# TriggerPI.net
KiCad netlist of a schematic drawn in EAGLE
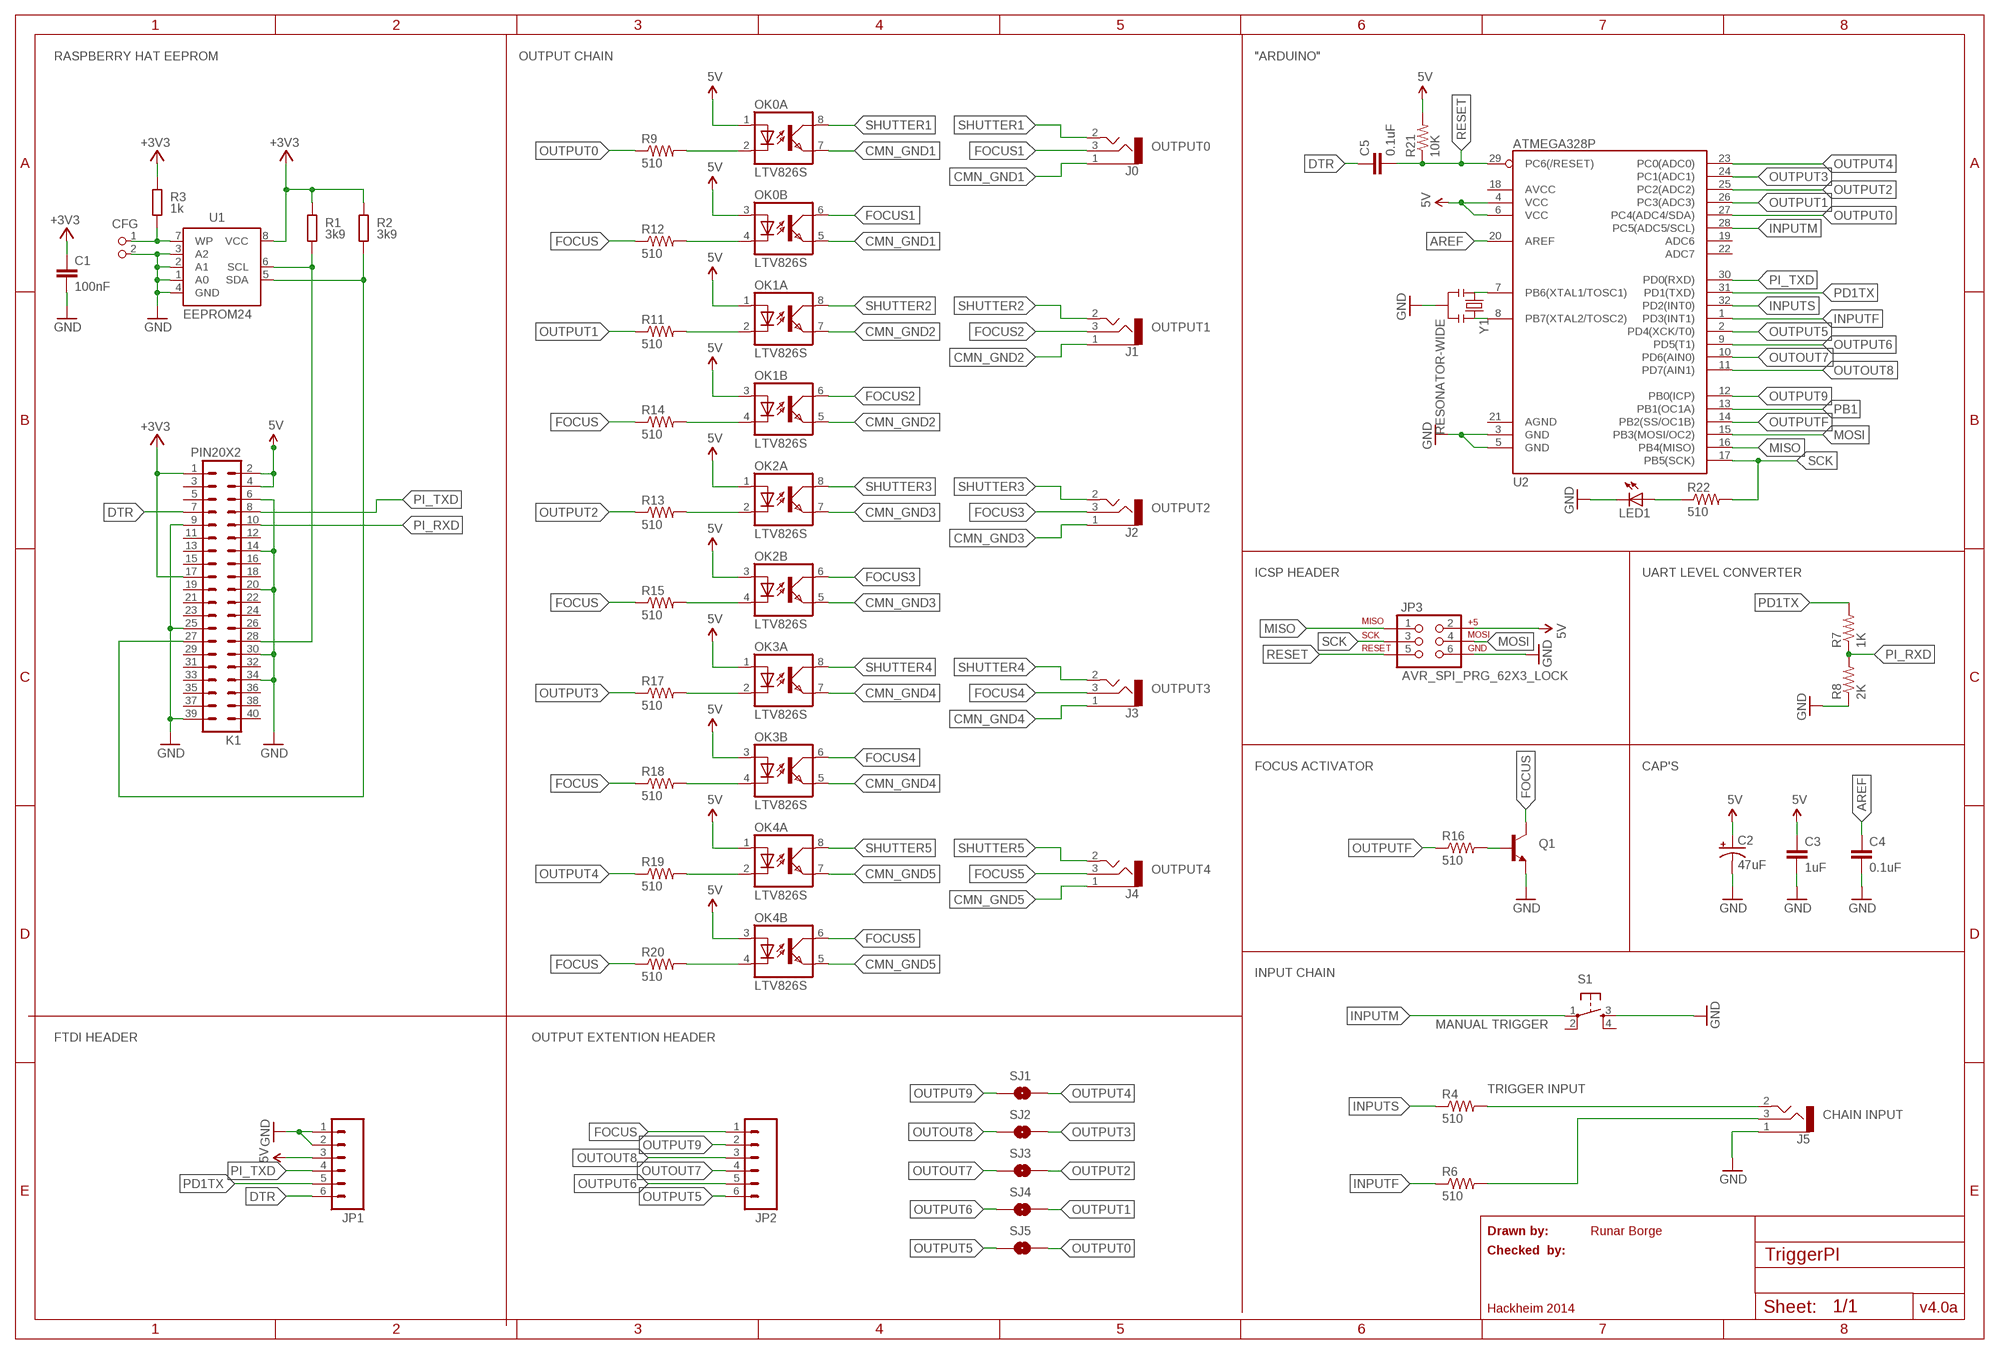
[diagram p0: schematic, sheet 1]

(export (version "E")
  (design (tool "Eeschema 10.0.6"))
  (components
    (comp (ref "C1")
      (value "100nF")
      (footprint "eagle-import:C0805K")
      (libsource (lib "eagle-import") (part "C-EUC0805K"))
    )
    (comp (ref "C2")
      (value "47uF")
      (footprint "eagle-import:EIA3528")
      (libsource (lib "eagle-import") (part "47UF-TANT"))
    )
    (comp (ref "C3")
      (value "1uF")
      (footprint "eagle-import:0805")
      (libsource (lib "eagle-import") (part "1UF-25V-10%(0805)"))
    )
    (comp (ref "C4")
      (value "0.1uF")
      (footprint "eagle-import:0603-CAP")
      (libsource (lib "eagle-import") (part "CAP0603-CAP"))
    )
    (comp (ref "C5")
      (value "0.1uF")
      (footprint "eagle-import:0603-CAP")
      (libsource (lib "eagle-import") (part "CAP0603-CAP"))
    )
    (comp (ref "CFG")
      (value "PIN2_100")
      (footprint "eagle-import:PIN_W_2")
      (libsource (lib "eagle-import") (part "PIN2_100"))
    )
    (comp (ref "J0")
      (value "AUDIO-3P'SJ-3523-SMT'")
      (footprint "eagle-import:3P-SMD-3.5")
      (libsource (lib "eagle-import") (part "AUDIO-3P'SJ-3523-SMT'"))
    )
    (comp (ref "J1")
      (value "AUDIO-3P'SJ-3523-SMT'")
      (footprint "eagle-import:3P-SMD-3.5")
      (libsource (lib "eagle-import") (part "AUDIO-3P'SJ-3523-SMT'"))
    )
    (comp (ref "J2")
      (value "AUDIO-3P'SJ-3523-SMT'")
      (footprint "eagle-import:3P-SMD-3.5")
      (libsource (lib "eagle-import") (part "AUDIO-3P'SJ-3523-SMT'"))
    )
    (comp (ref "J3")
      (value "AUDIO-3P'SJ-3523-SMT'")
      (footprint "eagle-import:3P-SMD-3.5")
      (libsource (lib "eagle-import") (part "AUDIO-3P'SJ-3523-SMT'"))
    )
    (comp (ref "J4")
      (value "AUDIO-3P'SJ-3523-SMT'")
      (footprint "eagle-import:3P-SMD-3.5")
      (libsource (lib "eagle-import") (part "AUDIO-3P'SJ-3523-SMT'"))
    )
    (comp (ref "J5")
      (value "AUDIO-3P'SJ-3523-SMT'")
      (footprint "eagle-import:3P-SMD-3.5")
      (libsource (lib "eagle-import") (part "AUDIO-3P'SJ-3523-SMT'"))
    )
    (comp (ref "JP1")
      (value "M06LOCK")
      (footprint "eagle-import:1X06_LOCK")
      (libsource (lib "eagle-import") (part "M06LOCK"))
    )
    (comp (ref "JP2")
      (value "M06LOCK")
      (footprint "eagle-import:1X06_LOCK")
      (libsource (lib "eagle-import") (part "M06LOCK"))
    )
    (comp (ref "JP3")
      (value "AVR_SPI_PRG_62X3_LOCK")
      (footprint "eagle-import:2X3_LOCK")
      (libsource (lib "eagle-import") (part "AVR_SPI_PRG_62X3_LOCK"))
    )
    (comp (ref "K1")
      (value "PIN20X2")
      (footprint "eagle-import:PIN_20X2")
      (libsource (lib "eagle-import") (part "PIN20X2"))
    )
    (comp (ref "LED1")
      (value "LED1206")
      (footprint "eagle-import:LED-1206")
      (libsource (lib "eagle-import") (part "LED1206"))
    )
    (comp (ref "OK0")
      (value "LTV826S")
      (footprint "eagle-import:DIL8-SMD")
      (fields (field (name "DIGIKEY") "160-1363-5-ND"))
      (libsource (lib "eagle-import") (part "LTV826S"))
    )
    (comp (ref "OK1")
      (value "LTV826S")
      (footprint "eagle-import:DIL8-SMD")
      (fields (field (name "DIGIKEY") "160-1363-5-ND"))
      (libsource (lib "eagle-import") (part "LTV826S"))
    )
    (comp (ref "OK2")
      (value "LTV826S")
      (footprint "eagle-import:DIL8-SMD")
      (fields (field (name "DIGIKEY") "160-1363-5-ND"))
      (libsource (lib "eagle-import") (part "LTV826S"))
    )
    (comp (ref "OK3")
      (value "LTV826S")
      (footprint "eagle-import:DIL8-SMD")
      (fields (field (name "DIGIKEY") "160-1363-5-ND"))
      (libsource (lib "eagle-import") (part "LTV826S"))
    )
    (comp (ref "OK4")
      (value "LTV826S")
      (footprint "eagle-import:DIL8-SMD")
      (fields (field (name "DIGIKEY") "160-1363-5-ND"))
      (libsource (lib "eagle-import") (part "LTV826S"))
    )
    (comp (ref "Q1")
      (value "TRANSISTOR_NPNSOT23-3")
      (footprint "eagle-import:SOT23-3")
      (libsource (lib "eagle-import") (part "TRANSISTOR_NPNSOT23-3"))
    )
    (comp (ref "R1")
      (value "3k9")
      (footprint "eagle-import:M0805")
      (fields (field (name "TOLERANCE") "5%"))
      (libsource (lib "eagle-import") (part "R-EU_M0805"))
    )
    (comp (ref "R2")
      (value "3k9")
      (footprint "eagle-import:M0805")
      (fields (field (name "TOLERANCE") "5%"))
      (libsource (lib "eagle-import") (part "R-EU_M0805"))
    )
    (comp (ref "R3")
      (value "1k")
      (footprint "eagle-import:M0805")
      (fields (field (name "TOLERANCE") "5%"))
      (libsource (lib "eagle-import") (part "R-EU_M0805"))
    )
    (comp (ref "R4")
      (value "510")
      (footprint "eagle-import:0603-RES")
      (libsource (lib "eagle-import") (part "RESISTOR0603-RES"))
    )
    (comp (ref "R6")
      (value "510")
      (footprint "eagle-import:0603-RES")
      (libsource (lib "eagle-import") (part "RESISTOR0603-RES"))
    )
    (comp (ref "R7")
      (value "1K")
      (footprint "eagle-import:0603-RES")
      (libsource (lib "eagle-import") (part "RESISTOR0603-RES"))
    )
    (comp (ref "R8")
      (value "2K")
      (footprint "eagle-import:0603-RES")
      (libsource (lib "eagle-import") (part "RESISTOR0603-RES"))
    )
    (comp (ref "R9")
      (value "510")
      (footprint "eagle-import:0603-RES")
      (libsource (lib "eagle-import") (part "RESISTOR0603-RES"))
    )
    (comp (ref "R11")
      (value "510")
      (footprint "eagle-import:0603-RES")
      (libsource (lib "eagle-import") (part "RESISTOR0603-RES"))
    )
    (comp (ref "R12")
      (value "510")
      (footprint "eagle-import:0603-RES")
      (libsource (lib "eagle-import") (part "RESISTOR0603-RES"))
    )
    (comp (ref "R13")
      (value "510")
      (footprint "eagle-import:0603-RES")
      (libsource (lib "eagle-import") (part "RESISTOR0603-RES"))
    )
    (comp (ref "R14")
      (value "510")
      (footprint "eagle-import:0603-RES")
      (libsource (lib "eagle-import") (part "RESISTOR0603-RES"))
    )
    (comp (ref "R15")
      (value "510")
      (footprint "eagle-import:0603-RES")
      (libsource (lib "eagle-import") (part "RESISTOR0603-RES"))
    )
    (comp (ref "R16")
      (value "510")
      (footprint "eagle-import:0603-RES")
      (libsource (lib "eagle-import") (part "RESISTOR0603-RES"))
    )
    (comp (ref "R17")
      (value "510")
      (footprint "eagle-import:0603-RES")
      (libsource (lib "eagle-import") (part "RESISTOR0603-RES"))
    )
    (comp (ref "R18")
      (value "510")
      (footprint "eagle-import:0603-RES")
      (libsource (lib "eagle-import") (part "RESISTOR0603-RES"))
    )
    (comp (ref "R19")
      (value "510")
      (footprint "eagle-import:0603-RES")
      (libsource (lib "eagle-import") (part "RESISTOR0603-RES"))
    )
    (comp (ref "R20")
      (value "510")
      (footprint "eagle-import:0603-RES")
      (libsource (lib "eagle-import") (part "RESISTOR0603-RES"))
    )
    (comp (ref "R21")
      (value "10K")
      (footprint "eagle-import:0603-RES")
      (libsource (lib "eagle-import") (part "RESISTOR0603-RES"))
    )
    (comp (ref "R22")
      (value "510")
      (footprint "eagle-import:0603-RES")
      (libsource (lib "eagle-import") (part "RESISTOR0603-RES"))
    )
    (comp (ref "S1")
      (value "TAC_SWITCHSMD")
      (footprint "eagle-import:TACTILE_SWITCH_SMD")
      (libsource (lib "eagle-import") (part "TAC_SWITCHSMD"))
    )
    (comp (ref "SJ1")
      (value "JUMPER-PAD-2-NOYES_SILK")
      (footprint "eagle-import:PAD-JUMPER-2-NO_YES_SILK")
      (libsource (lib "eagle-import") (part "JUMPER-PAD-2-NOYES_SILK"))
    )
    (comp (ref "SJ2")
      (value "JUMPER-PAD-2-NOYES_SILK")
      (footprint "eagle-import:PAD-JUMPER-2-NO_YES_SILK")
      (libsource (lib "eagle-import") (part "JUMPER-PAD-2-NOYES_SILK"))
    )
    (comp (ref "SJ3")
      (value "JUMPER-PAD-2-NOYES_SILK")
      (footprint "eagle-import:PAD-JUMPER-2-NO_YES_SILK")
      (libsource (lib "eagle-import") (part "JUMPER-PAD-2-NOYES_SILK"))
    )
    (comp (ref "SJ4")
      (value "JUMPER-PAD-2-NOYES_SILK")
      (footprint "eagle-import:PAD-JUMPER-2-NO_YES_SILK")
      (libsource (lib "eagle-import") (part "JUMPER-PAD-2-NOYES_SILK"))
    )
    (comp (ref "SJ5")
      (value "JUMPER-PAD-2-NOYES_SILK")
      (footprint "eagle-import:PAD-JUMPER-2-NO_YES_SILK")
      (libsource (lib "eagle-import") (part "JUMPER-PAD-2-NOYES_SILK"))
    )
    (comp (ref "U1")
      (value "EEPROM24")
      (footprint "eagle-import:SOIC8")
      (libsource (lib "eagle-import") (part "EEPROM24"))
    )
    (comp (ref "U2")
      (value "ATMEGA328P")
      (footprint "eagle-import:TQFP32-08")
      (libsource (lib "eagle-import") (part "ATMEGA328_SMT"))
    )
    (comp (ref "Y1")
      (value "RESONATOR-WIDE")
      (footprint "eagle-import:RESONATOR-WIDE-SMD")
      (libsource (lib "eagle-import") (part "RESONATOR-WIDE"))
    )
  )
  (nets
    (net (code "1") (name "+3V3") (class "Default")
      (node (ref "C1") (pin "1") (pinfunction "1_1") (pintype "passive"))
      (node (ref "K1") (pin "1") (pinfunction "1_1") (pintype "passive"))
      (node (ref "K1") (pin "17") (pinfunction "17_17") (pintype "passive"))
      (node (ref "R1") (pin "2") (pinfunction "2_2") (pintype "passive"))
      (node (ref "R2") (pin "2") (pinfunction "2_2") (pintype "passive"))
      (node (ref "R3") (pin "2") (pinfunction "2_2") (pintype "passive"))
      (node (ref "U1") (pin "8") (pinfunction "VCC_8") (pintype "power_in"))
    )
    (net (code "2") (name "5V") (class "Default")
      (node (ref "C2") (pin "A") (pinfunction "+_A") (pintype "passive"))
      (node (ref "C3") (pin "1") (pinfunction "1_1") (pintype "passive"))
      (node (ref "JP1") (pin "3") (pinfunction "3_3") (pintype "passive"))
      (node (ref "JP3") (pin "2") (pinfunction "2_2") (pintype "passive"))
      (node (ref "K1") (pin "2") (pinfunction "2_2") (pintype "passive"))
      (node (ref "K1") (pin "4") (pinfunction "4_4") (pintype "passive"))
      (node (ref "OK0") (pin "1") (pinfunction "A_1") (pintype "passive"))
      (node (ref "OK0") (pin "3") (pinfunction "A_3") (pintype "passive"))
      (node (ref "OK1") (pin "1") (pinfunction "A_1") (pintype "passive"))
      (node (ref "OK1") (pin "3") (pinfunction "A_3") (pintype "passive"))
      (node (ref "OK2") (pin "1") (pinfunction "A_1") (pintype "passive"))
      (node (ref "OK2") (pin "3") (pinfunction "A_3") (pintype "passive"))
      (node (ref "OK3") (pin "1") (pinfunction "A_1") (pintype "passive"))
      (node (ref "OK3") (pin "3") (pinfunction "A_3") (pintype "passive"))
      (node (ref "OK4") (pin "1") (pinfunction "A_1") (pintype "passive"))
      (node (ref "OK4") (pin "3") (pinfunction "A_3") (pintype "passive"))
      (node (ref "R21") (pin "2") (pinfunction "2_2") (pintype "passive"))
      (node (ref "U2") (pin "4") (pinfunction "VCC_4") (pintype "bidirectional"))
      (node (ref "U2") (pin "6") (pinfunction "VCC_6") (pintype "bidirectional"))
    )
    (net (code "3") (name "AREF") (class "Default")
      (node (ref "C4") (pin "1") (pinfunction "1_1") (pintype "passive"))
      (node (ref "U2") (pin "20") (pinfunction "AREF_20") (pintype "bidirectional"))
    )
    (net (code "4") (name "CMN_GND1") (class "Default")
      (node (ref "J0") (pin "1") (pinfunction "1_1") (pintype "bidirectional"))
      (node (ref "OK0") (pin "5") (pinfunction "EMIT_5") (pintype "passive"))
      (node (ref "OK0") (pin "7") (pinfunction "EMIT_7") (pintype "passive"))
    )
    (net (code "5") (name "CMN_GND2") (class "Default")
      (node (ref "J1") (pin "1") (pinfunction "1_1") (pintype "bidirectional"))
      (node (ref "OK1") (pin "5") (pinfunction "EMIT_5") (pintype "passive"))
      (node (ref "OK1") (pin "7") (pinfunction "EMIT_7") (pintype "passive"))
    )
    (net (code "6") (name "CMN_GND3") (class "Default")
      (node (ref "J2") (pin "1") (pinfunction "1_1") (pintype "bidirectional"))
      (node (ref "OK2") (pin "5") (pinfunction "EMIT_5") (pintype "passive"))
      (node (ref "OK2") (pin "7") (pinfunction "EMIT_7") (pintype "passive"))
    )
    (net (code "7") (name "CMN_GND4") (class "Default")
      (node (ref "J3") (pin "1") (pinfunction "1_1") (pintype "bidirectional"))
      (node (ref "OK3") (pin "5") (pinfunction "EMIT_5") (pintype "passive"))
      (node (ref "OK3") (pin "7") (pinfunction "EMIT_7") (pintype "passive"))
    )
    (net (code "8") (name "CMN_GND5") (class "Default")
      (node (ref "J4") (pin "1") (pinfunction "1_1") (pintype "bidirectional"))
      (node (ref "OK4") (pin "5") (pinfunction "EMIT_5") (pintype "passive"))
      (node (ref "OK4") (pin "7") (pinfunction "EMIT_7") (pintype "passive"))
    )
    (net (code "9") (name "DTR") (class "Default")
      (node (ref "C5") (pin "1") (pinfunction "1_1") (pintype "passive"))
      (node (ref "JP1") (pin "6") (pinfunction "6_6") (pintype "passive"))
      (node (ref "K1") (pin "7") (pinfunction "7_7") (pintype "passive"))
    )
    (net (code "10") (name "FOCUS") (class "Default")
      (node (ref "JP2") (pin "1") (pinfunction "1_1") (pintype "passive"))
      (node (ref "Q1") (pin "3") (pinfunction "C_3") (pintype "passive"))
      (node (ref "R12") (pin "1") (pinfunction "1_1") (pintype "passive"))
      (node (ref "R14") (pin "1") (pinfunction "1_1") (pintype "passive"))
      (node (ref "R15") (pin "1") (pinfunction "1_1") (pintype "passive"))
      (node (ref "R18") (pin "1") (pinfunction "1_1") (pintype "passive"))
      (node (ref "R20") (pin "1") (pinfunction "1_1") (pintype "passive"))
    )
    (net (code "11") (name "FOCUS1") (class "Default")
      (node (ref "J0") (pin "3") (pinfunction "2_3") (pintype "bidirectional"))
      (node (ref "OK0") (pin "6") (pinfunction "COL_6") (pintype "passive"))
    )
    (net (code "12") (name "FOCUS2") (class "Default")
      (node (ref "J1") (pin "3") (pinfunction "2_3") (pintype "bidirectional"))
      (node (ref "OK1") (pin "6") (pinfunction "COL_6") (pintype "passive"))
    )
    (net (code "13") (name "FOCUS3") (class "Default")
      (node (ref "J2") (pin "3") (pinfunction "2_3") (pintype "bidirectional"))
      (node (ref "OK2") (pin "6") (pinfunction "COL_6") (pintype "passive"))
    )
    (net (code "14") (name "FOCUS4") (class "Default")
      (node (ref "J3") (pin "3") (pinfunction "2_3") (pintype "bidirectional"))
      (node (ref "OK3") (pin "6") (pinfunction "COL_6") (pintype "passive"))
    )
    (net (code "15") (name "FOCUS5") (class "Default")
      (node (ref "J4") (pin "3") (pinfunction "2_3") (pintype "bidirectional"))
      (node (ref "OK4") (pin "6") (pinfunction "COL_6") (pintype "passive"))
    )
    (net (code "16") (name "GND") (class "Default")
      (node (ref "C1") (pin "2") (pinfunction "2_2") (pintype "passive"))
      (node (ref "C2") (pin "C") (pinfunction "-_C") (pintype "passive"))
      (node (ref "C3") (pin "2") (pinfunction "2_2") (pintype "passive"))
      (node (ref "C4") (pin "2") (pinfunction "2_2") (pintype "passive"))
      (node (ref "CFG") (pin "2") (pinfunction "2_2") (pintype "passive"))
      (node (ref "J5") (pin "1") (pinfunction "1_1") (pintype "bidirectional"))
      (node (ref "JP1") (pin "1") (pinfunction "1_1") (pintype "passive"))
      (node (ref "JP1") (pin "2") (pinfunction "2_2") (pintype "passive"))
      (node (ref "JP3") (pin "6") (pinfunction "6_6") (pintype "passive"))
      (node (ref "K1") (pin "14") (pinfunction "14_14") (pintype "passive"))
      (node (ref "K1") (pin "20") (pinfunction "20_20") (pintype "passive"))
      (node (ref "K1") (pin "25") (pinfunction "25_25") (pintype "passive"))
      (node (ref "K1") (pin "30") (pinfunction "30_30") (pintype "passive"))
      (node (ref "K1") (pin "34") (pinfunction "34_34") (pintype "passive"))
      (node (ref "K1") (pin "39") (pinfunction "39_39") (pintype "passive"))
      (node (ref "K1") (pin "6") (pinfunction "6_6") (pintype "passive"))
      (node (ref "K1") (pin "9") (pinfunction "9_9") (pintype "passive"))
      (node (ref "LED1") (pin "C") (pinfunction "C_C") (pintype "passive"))
      (node (ref "Q1") (pin "2") (pinfunction "E_2") (pintype "passive"))
      (node (ref "R8") (pin "1") (pinfunction "1_1") (pintype "passive"))
      (node (ref "S1") (pin "3") (pinfunction "3_3") (pintype "passive"))
      (node (ref "U1") (pin "1") (pinfunction "A0_1") (pintype "input"))
      (node (ref "U1") (pin "2") (pinfunction "A1_2") (pintype "input"))
      (node (ref "U1") (pin "3") (pinfunction "A2_3") (pintype "input"))
      (node (ref "U1") (pin "4") (pinfunction "GND_4") (pintype "power_in"))
      (node (ref "U2") (pin "3") (pinfunction "GND_3") (pintype "bidirectional"))
      (node (ref "U2") (pin "5") (pinfunction "GND_5") (pintype "bidirectional"))
      (node (ref "Y1") (pin "2") (pinfunction "2_2") (pintype "passive"))
    )
    (net (code "17") (name "INPUTF") (class "Default")
      (node (ref "R6") (pin "1") (pinfunction "1_1") (pintype "passive"))
      (node (ref "U2") (pin "1") (pinfunction "PD3(INT1)_1") (pintype "bidirectional"))
    )
    (net (code "18") (name "INPUTM") (class "Default")
      (node (ref "S1") (pin "1") (pinfunction "1_1") (pintype "passive"))
      (node (ref "U2") (pin "28") (pinfunction "PC5(ADC5/SCL)_28") (pintype "bidirectional"))
    )
    (net (code "19") (name "INPUTS") (class "Default")
      (node (ref "R4") (pin "1") (pinfunction "1_1") (pintype "passive"))
      (node (ref "U2") (pin "32") (pinfunction "PD2(INT0)_32") (pintype "bidirectional"))
    )
    (net (code "20") (name "MISO") (class "Default")
      (node (ref "JP3") (pin "1") (pinfunction "1_1") (pintype "passive"))
      (node (ref "U2") (pin "16") (pinfunction "PB4(MISO)_16") (pintype "bidirectional"))
    )
    (net (code "21") (name "MOSI") (class "Default")
      (node (ref "JP3") (pin "4") (pinfunction "4_4") (pintype "passive"))
      (node (ref "U2") (pin "15") (pinfunction "PB3(MOSI/OC2)_15") (pintype "bidirectional"))
    )
    (net (code "22") (name "Net-(J5-2)") (class "Default")
      (node (ref "J5") (pin "3") (pinfunction "2_3") (pintype "bidirectional"))
      (node (ref "R6") (pin "2") (pinfunction "2_2") (pintype "passive"))
    )
    (net (code "23") (name "Net-(J5-5)") (class "Default")
      (node (ref "J5") (pin "2") (pinfunction "5_2") (pintype "bidirectional"))
      (node (ref "R4") (pin "2") (pinfunction "2_2") (pintype "passive"))
    )
    (net (code "24") (name "Net-(LED1-PadA)") (class "Default")
      (node (ref "LED1") (pin "A") (pinfunction "A_A") (pintype "passive"))
      (node (ref "R22") (pin "1") (pinfunction "1_1") (pintype "passive"))
    )
    (net (code "25") (name "Net-(OK0A-C)") (class "Default")
      (node (ref "OK0") (pin "2") (pinfunction "C_2") (pintype "passive"))
      (node (ref "R9") (pin "2") (pinfunction "2_2") (pintype "passive"))
    )
    (net (code "26") (name "Net-(OK0B-C)") (class "Default")
      (node (ref "OK0") (pin "4") (pinfunction "C_4") (pintype "passive"))
      (node (ref "R12") (pin "2") (pinfunction "2_2") (pintype "passive"))
    )
    (net (code "27") (name "Net-(OK1A-C)") (class "Default")
      (node (ref "OK1") (pin "2") (pinfunction "C_2") (pintype "passive"))
      (node (ref "R11") (pin "2") (pinfunction "2_2") (pintype "passive"))
    )
    (net (code "28") (name "Net-(OK1B-C)") (class "Default")
      (node (ref "OK1") (pin "4") (pinfunction "C_4") (pintype "passive"))
      (node (ref "R14") (pin "2") (pinfunction "2_2") (pintype "passive"))
    )
    (net (code "29") (name "Net-(OK2A-C)") (class "Default")
      (node (ref "OK2") (pin "2") (pinfunction "C_2") (pintype "passive"))
      (node (ref "R13") (pin "2") (pinfunction "2_2") (pintype "passive"))
    )
    (net (code "30") (name "Net-(OK2B-C)") (class "Default")
      (node (ref "OK2") (pin "4") (pinfunction "C_4") (pintype "passive"))
      (node (ref "R15") (pin "2") (pinfunction "2_2") (pintype "passive"))
    )
    (net (code "31") (name "Net-(OK3A-C)") (class "Default")
      (node (ref "OK3") (pin "2") (pinfunction "C_2") (pintype "passive"))
      (node (ref "R17") (pin "2") (pinfunction "2_2") (pintype "passive"))
    )
    (net (code "32") (name "Net-(OK3B-C)") (class "Default")
      (node (ref "OK3") (pin "4") (pinfunction "C_4") (pintype "passive"))
      (node (ref "R18") (pin "2") (pinfunction "2_2") (pintype "passive"))
    )
    (net (code "33") (name "Net-(OK4A-C)") (class "Default")
      (node (ref "OK4") (pin "2") (pinfunction "C_2") (pintype "passive"))
      (node (ref "R19") (pin "2") (pinfunction "2_2") (pintype "passive"))
    )
    (net (code "34") (name "Net-(OK4B-C)") (class "Default")
      (node (ref "OK4") (pin "4") (pinfunction "C_4") (pintype "passive"))
      (node (ref "R20") (pin "2") (pinfunction "2_2") (pintype "passive"))
    )
    (net (code "35") (name "Net-(Q1-B)") (class "Default")
      (node (ref "Q1") (pin "1") (pinfunction "B_1") (pintype "passive"))
      (node (ref "R16") (pin "2") (pinfunction "2_2") (pintype "passive"))
    )
    (net (code "36") (name "Net-(U1-SCL)") (class "Default")
      (node (ref "K1") (pin "28") (pinfunction "28_28") (pintype "passive"))
      (node (ref "R1") (pin "1") (pinfunction "1_1") (pintype "passive"))
      (node (ref "U1") (pin "6") (pinfunction "SCL_6") (pintype "input"))
    )
    (net (code "37") (name "Net-(U1-SDA)") (class "Default")
      (node (ref "K1") (pin "27") (pinfunction "27_27") (pintype "passive"))
      (node (ref "R2") (pin "1") (pinfunction "1_1") (pintype "passive"))
      (node (ref "U1") (pin "5") (pinfunction "SDA_5") (pintype "bidirectional"))
    )
    (net (code "38") (name "Net-(U1-WP)") (class "Default")
      (node (ref "CFG") (pin "1") (pinfunction "1_1") (pintype "passive"))
      (node (ref "R3") (pin "1") (pinfunction "1_1") (pintype "passive"))
      (node (ref "U1") (pin "7") (pinfunction "WP_7") (pintype "input"))
    )
    (net (code "39") (name "Net-(U2-PB6(XTAL1{slash}TOSC1))") (class "Default")
      (node (ref "U2") (pin "7") (pinfunction "PB6(XTAL1/TOSC1)_7") (pintype "bidirectional"))
      (node (ref "Y1") (pin "1") (pinfunction "1_1") (pintype "passive"))
    )
    (net (code "40") (name "Net-(U2-PB7(XTAL2{slash}TOSC2))") (class "Default")
      (node (ref "U2") (pin "8") (pinfunction "PB7(XTAL2/TOSC2)_8") (pintype "bidirectional"))
      (node (ref "Y1") (pin "3") (pinfunction "3_3") (pintype "passive"))
    )
    (net (code "41") (name "OUTOUT7") (class "Default")
      (node (ref "JP2") (pin "4") (pinfunction "4_4") (pintype "passive"))
      (node (ref "SJ3") (pin "1") (pinfunction "1_1") (pintype "passive"))
      (node (ref "U2") (pin "10") (pinfunction "PD6(AIN0)_10") (pintype "bidirectional"))
    )
    (net (code "42") (name "OUTOUT8") (class "Default")
      (node (ref "JP2") (pin "3") (pinfunction "3_3") (pintype "passive"))
      (node (ref "SJ2") (pin "1") (pinfunction "1_1") (pintype "passive"))
      (node (ref "U2") (pin "11") (pinfunction "PD7(AIN1)_11") (pintype "bidirectional"))
    )
    (net (code "43") (name "OUTPUT0") (class "Default")
      (node (ref "R9") (pin "1") (pinfunction "1_1") (pintype "passive"))
      (node (ref "SJ5") (pin "2") (pinfunction "2_2") (pintype "passive"))
      (node (ref "U2") (pin "27") (pinfunction "PC4(ADC4/SDA)_27") (pintype "bidirectional"))
    )
    (net (code "44") (name "OUTPUT1") (class "Default")
      (node (ref "R11") (pin "1") (pinfunction "1_1") (pintype "passive"))
      (node (ref "SJ4") (pin "2") (pinfunction "2_2") (pintype "passive"))
      (node (ref "U2") (pin "26") (pinfunction "PC3(ADC3)_26") (pintype "bidirectional"))
    )
    (net (code "45") (name "OUTPUT2") (class "Default")
      (node (ref "R13") (pin "1") (pinfunction "1_1") (pintype "passive"))
      (node (ref "SJ3") (pin "2") (pinfunction "2_2") (pintype "passive"))
      (node (ref "U2") (pin "25") (pinfunction "PC2(ADC2)_25") (pintype "bidirectional"))
    )
    (net (code "46") (name "OUTPUT3") (class "Default")
      (node (ref "R17") (pin "1") (pinfunction "1_1") (pintype "passive"))
      (node (ref "SJ2") (pin "2") (pinfunction "2_2") (pintype "passive"))
      (node (ref "U2") (pin "24") (pinfunction "PC1(ADC1)_24") (pintype "bidirectional"))
    )
    (net (code "47") (name "OUTPUT4") (class "Default")
      (node (ref "R19") (pin "1") (pinfunction "1_1") (pintype "passive"))
      (node (ref "SJ1") (pin "2") (pinfunction "2_2") (pintype "passive"))
      (node (ref "U2") (pin "23") (pinfunction "PC0(ADC0)_23") (pintype "bidirectional"))
    )
    (net (code "48") (name "OUTPUT5") (class "Default")
      (node (ref "JP2") (pin "6") (pinfunction "6_6") (pintype "passive"))
      (node (ref "SJ5") (pin "1") (pinfunction "1_1") (pintype "passive"))
      (node (ref "U2") (pin "2") (pinfunction "PD4(XCK/T0)_2") (pintype "bidirectional"))
    )
    (net (code "49") (name "OUTPUT6") (class "Default")
      (node (ref "JP2") (pin "5") (pinfunction "5_5") (pintype "passive"))
      (node (ref "SJ4") (pin "1") (pinfunction "1_1") (pintype "passive"))
      (node (ref "U2") (pin "9") (pinfunction "PD5(T1)_9") (pintype "bidirectional"))
    )
    (net (code "50") (name "OUTPUT9") (class "Default")
      (node (ref "JP2") (pin "2") (pinfunction "2_2") (pintype "passive"))
      (node (ref "SJ1") (pin "1") (pinfunction "1_1") (pintype "passive"))
      (node (ref "U2") (pin "12") (pinfunction "PB0(ICP)_12") (pintype "bidirectional"))
    )
    (net (code "51") (name "OUTPUTF") (class "Default")
      (node (ref "R16") (pin "1") (pinfunction "1_1") (pintype "passive"))
      (node (ref "U2") (pin "14") (pinfunction "PB2(SS/OC1B)_14") (pintype "bidirectional"))
    )
    (net (code "52") (name "PB1") (class "Default")
      (node (ref "U2") (pin "13") (pinfunction "PB1(OC1A)_13") (pintype "bidirectional"))
    )
    (net (code "53") (name "PD1TX") (class "Default")
      (node (ref "JP1") (pin "5") (pinfunction "5_5") (pintype "passive"))
      (node (ref "R7") (pin "2") (pinfunction "2_2") (pintype "passive"))
      (node (ref "U2") (pin "31") (pinfunction "PD1(TXD)_31") (pintype "bidirectional"))
    )
    (net (code "54") (name "PI_RXD") (class "Default")
      (node (ref "K1") (pin "10") (pinfunction "10_10") (pintype "passive"))
      (node (ref "R7") (pin "1") (pinfunction "1_1") (pintype "passive"))
      (node (ref "R8") (pin "2") (pinfunction "2_2") (pintype "passive"))
    )
    (net (code "55") (name "PI_TXD") (class "Default")
      (node (ref "JP1") (pin "4") (pinfunction "4_4") (pintype "passive"))
      (node (ref "K1") (pin "8") (pinfunction "8_8") (pintype "passive"))
      (node (ref "U2") (pin "30") (pinfunction "PD0(RXD)_30") (pintype "bidirectional"))
    )
    (net (code "56") (name "RESET") (class "Default")
      (node (ref "C5") (pin "2") (pinfunction "2_2") (pintype "passive"))
      (node (ref "JP3") (pin "5") (pinfunction "5_5") (pintype "passive"))
      (node (ref "R21") (pin "1") (pinfunction "1_1") (pintype "passive"))
      (node (ref "U2") (pin "29") (pinfunction "PC6(/RESET)_29") (pintype "bidirectional"))
    )
    (net (code "57") (name "SCK") (class "Default")
      (node (ref "JP3") (pin "3") (pinfunction "3_3") (pintype "passive"))
      (node (ref "R22") (pin "2") (pinfunction "2_2") (pintype "passive"))
      (node (ref "U2") (pin "17") (pinfunction "PB5(SCK)_17") (pintype "bidirectional"))
    )
    (net (code "58") (name "SHUTTER1") (class "Default")
      (node (ref "J0") (pin "2") (pinfunction "5_2") (pintype "bidirectional"))
      (node (ref "OK0") (pin "8") (pinfunction "COL_8") (pintype "passive"))
    )
    (net (code "59") (name "SHUTTER2") (class "Default")
      (node (ref "J1") (pin "2") (pinfunction "5_2") (pintype "bidirectional"))
      (node (ref "OK1") (pin "8") (pinfunction "COL_8") (pintype "passive"))
    )
    (net (code "60") (name "SHUTTER3") (class "Default")
      (node (ref "J2") (pin "2") (pinfunction "5_2") (pintype "bidirectional"))
      (node (ref "OK2") (pin "8") (pinfunction "COL_8") (pintype "passive"))
    )
    (net (code "61") (name "SHUTTER4") (class "Default")
      (node (ref "J3") (pin "2") (pinfunction "5_2") (pintype "bidirectional"))
      (node (ref "OK3") (pin "8") (pinfunction "COL_8") (pintype "passive"))
    )
    (net (code "62") (name "SHUTTER5") (class "Default")
      (node (ref "J4") (pin "2") (pinfunction "5_2") (pintype "bidirectional"))
      (node (ref "OK4") (pin "8") (pinfunction "COL_8") (pintype "passive"))
    )
    (net (code "63") (name "unconnected-(K1-Pad3)") (class "Default")
      (node (ref "K1") (pin "3") (pinfunction "3_3") (pintype "passive"))
    )
    (net (code "64") (name "unconnected-(K1-Pad5)") (class "Default")
      (node (ref "K1") (pin "5") (pinfunction "5_5") (pintype "passive"))
    )
    (net (code "65") (name "unconnected-(K1-Pad11)") (class "Default")
      (node (ref "K1") (pin "11") (pinfunction "11_11") (pintype "passive"))
    )
    (net (code "66") (name "unconnected-(K1-Pad12)") (class "Default")
      (node (ref "K1") (pin "12") (pinfunction "12_12") (pintype "passive"))
    )
    (net (code "67") (name "unconnected-(K1-Pad13)") (class "Default")
      (node (ref "K1") (pin "13") (pinfunction "13_13") (pintype "passive"))
    )
    (net (code "68") (name "unconnected-(K1-Pad15)") (class "Default")
      (node (ref "K1") (pin "15") (pinfunction "15_15") (pintype "passive"))
    )
    (net (code "69") (name "unconnected-(K1-Pad16)") (class "Default")
      (node (ref "K1") (pin "16") (pinfunction "16_16") (pintype "passive"))
    )
    (net (code "70") (name "unconnected-(K1-Pad18)") (class "Default")
      (node (ref "K1") (pin "18") (pinfunction "18_18") (pintype "passive"))
    )
    (net (code "71") (name "unconnected-(K1-Pad19)") (class "Default")
      (node (ref "K1") (pin "19") (pinfunction "19_19") (pintype "passive"))
    )
    (net (code "72") (name "unconnected-(K1-Pad21)") (class "Default")
      (node (ref "K1") (pin "21") (pinfunction "21_21") (pintype "passive"))
    )
    (net (code "73") (name "unconnected-(K1-Pad22)") (class "Default")
      (node (ref "K1") (pin "22") (pinfunction "22_22") (pintype "passive"))
    )
    (net (code "74") (name "unconnected-(K1-Pad23)") (class "Default")
      (node (ref "K1") (pin "23") (pinfunction "23_23") (pintype "passive"))
    )
    (net (code "75") (name "unconnected-(K1-Pad24)") (class "Default")
      (node (ref "K1") (pin "24") (pinfunction "24_24") (pintype "passive"))
    )
    (net (code "76") (name "unconnected-(K1-Pad26)") (class "Default")
      (node (ref "K1") (pin "26") (pinfunction "26_26") (pintype "passive"))
    )
    (net (code "77") (name "unconnected-(K1-Pad29)") (class "Default")
      (node (ref "K1") (pin "29") (pinfunction "29_29") (pintype "passive"))
    )
    (net (code "78") (name "unconnected-(K1-Pad31)") (class "Default")
      (node (ref "K1") (pin "31") (pinfunction "31_31") (pintype "passive"))
    )
    (net (code "79") (name "unconnected-(K1-Pad32)") (class "Default")
      (node (ref "K1") (pin "32") (pinfunction "32_32") (pintype "passive"))
    )
    (net (code "80") (name "unconnected-(K1-Pad33)") (class "Default")
      (node (ref "K1") (pin "33") (pinfunction "33_33") (pintype "passive"))
    )
    (net (code "81") (name "unconnected-(K1-Pad35)") (class "Default")
      (node (ref "K1") (pin "35") (pinfunction "35_35") (pintype "passive"))
    )
    (net (code "82") (name "unconnected-(K1-Pad36)") (class "Default")
      (node (ref "K1") (pin "36") (pinfunction "36_36") (pintype "passive"))
    )
    (net (code "83") (name "unconnected-(K1-Pad37)") (class "Default")
      (node (ref "K1") (pin "37") (pinfunction "37_37") (pintype "passive"))
    )
    (net (code "84") (name "unconnected-(K1-Pad38)") (class "Default")
      (node (ref "K1") (pin "38") (pinfunction "38_38") (pintype "passive"))
    )
    (net (code "85") (name "unconnected-(K1-Pad40)") (class "Default")
      (node (ref "K1") (pin "40") (pinfunction "40_40") (pintype "passive"))
    )
    (net (code "86") (name "unconnected-(S1-Pad2)") (class "Default")
      (node (ref "S1") (pin "2") (pinfunction "2_2") (pintype "passive"))
    )
    (net (code "87") (name "unconnected-(S1-Pad4)") (class "Default")
      (node (ref "S1") (pin "4") (pinfunction "4_4") (pintype "passive"))
    )
    (net (code "88") (name "unconnected-(U2-ADC6-Pad19)") (class "Default")
      (node (ref "U2") (pin "19") (pinfunction "ADC6_19") (pintype "bidirectional"))
    )
    (net (code "89") (name "unconnected-(U2-ADC7-Pad22)") (class "Default")
      (node (ref "U2") (pin "22") (pinfunction "ADC7_22") (pintype "bidirectional"))
    )
    (net (code "90") (name "unconnected-(U2-AGND-Pad21)") (class "Default")
      (node (ref "U2") (pin "21") (pinfunction "AGND_21") (pintype "bidirectional"))
    )
    (net (code "91") (name "unconnected-(U2-AVCC-Pad18)") (class "Default")
      (node (ref "U2") (pin "18") (pinfunction "AVCC_18") (pintype "bidirectional"))
    )
  )
)
